# Power_Circuit.net
KiCad netlist of a schematic drawn in Altium Designer
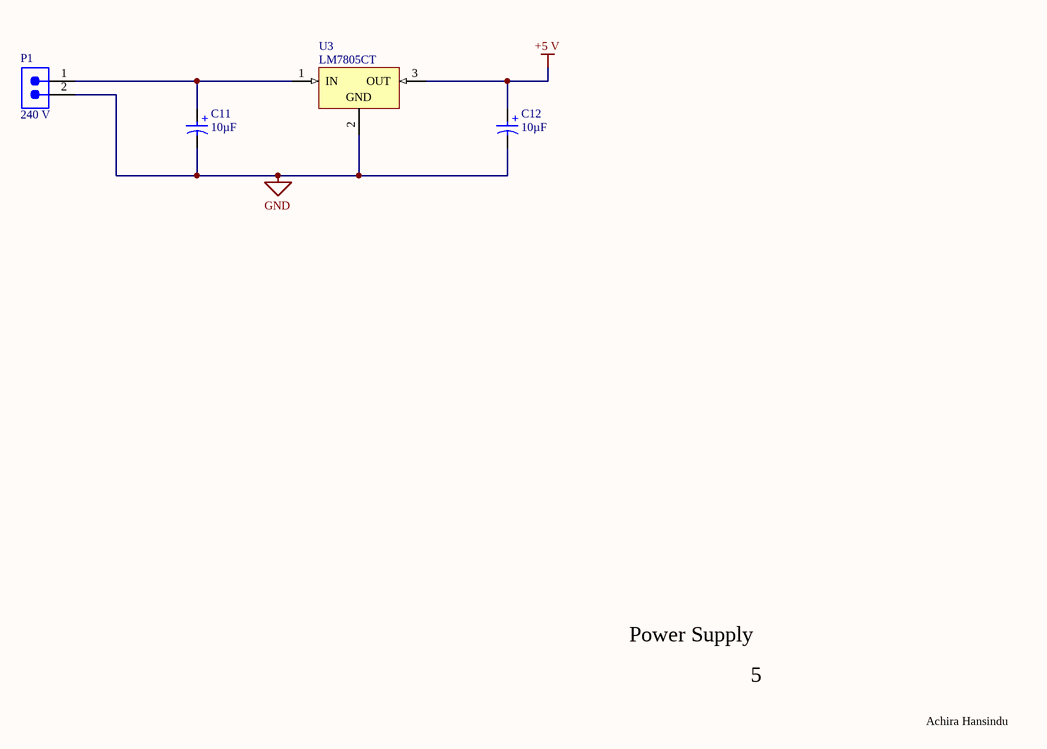
[diagram p0: Power Circuit.SchDoc]

(export (version "E")
  (design (tool "Eeschema 10.0.6"))
  (components
    (comp (ref "C11")
      (value "870575873001")
      (footprint "WCAP-HTG5_D6.3H8")
      (description "870575873001 Cap, 10Uf, 63V, Alu Elec, Hybrid, Rad Rohs Compliant: Yes")
      (fields (field (name "CAPACITANCE") "10µF"))
      (libsource (lib "Altium Content Vault") (part "Capacitor_Polarized"))
    )
    (comp (ref "C12")
      (value "870575873001")
      (footprint "WCAP-HTG5_D6.3H8")
      (description "870575873001 Cap, 10Uf, 63V, Alu Elec, Hybrid, Rad Rohs Compliant: Yes")
      (fields (field (name "CAPACITANCE") "10µF"))
      (libsource (lib "Altium Content Vault") (part "Capacitor_Polarized"))
    )
    (comp (ref "P1")
      (value "240 V")
      (footprint "691322110002")
      (fields (field (name "VOLTAGE") "300V"))
      (libsource (lib "Altium Content Vault") (part "TBL - 1R - 02P - Male"))
    )
    (comp (ref "U3")
      (value "LM7805CT")
      (footprint "FAIR-TO-220-3")
      (description "Positive Voltage Regulator, 5 V, 1 A, -40 to 125 degC, 3-Pin TO-220, RoHS, Tube")
      (fields (field (name "MANUFACTURER") "FairchildSemiconductor"))
      (libsource (lib "Altium Content Vault") (part "FAIR-LM7805CT-TO220-3"))
    )
  )
  (nets
    (net (code "1") (name "+5 V") (class "Default")
      (node (ref "C12") (pin "1") (pinfunction "P_1") (pintype "passive"))
      (node (ref "U3") (pin "3") (pinfunction "OUT_3") (pintype "input"))
    )
    (net (code "2") (name "GND") (class "Default")
      (node (ref "C11") (pin "2") (pinfunction "N_2") (pintype "passive"))
      (node (ref "C12") (pin "2") (pinfunction "N_2") (pintype "passive"))
      (node (ref "P1") (pin "2") (pinfunction "2_2") (pintype "passive"))
      (node (ref "U3") (pin "2") (pinfunction "GND_2") (pintype "power_in"))
    )
    (net (code "3") (name "Net-(C11-P)") (class "Default")
      (node (ref "C11") (pin "1") (pinfunction "P_1") (pintype "passive"))
      (node (ref "P1") (pin "1") (pinfunction "1_1") (pintype "passive"))
      (node (ref "U3") (pin "1") (pinfunction "IN_1") (pintype "input"))
    )
  )
)
